# DualMonoPSU.net
KiCad netlist of a schematic drawn in EAGLE
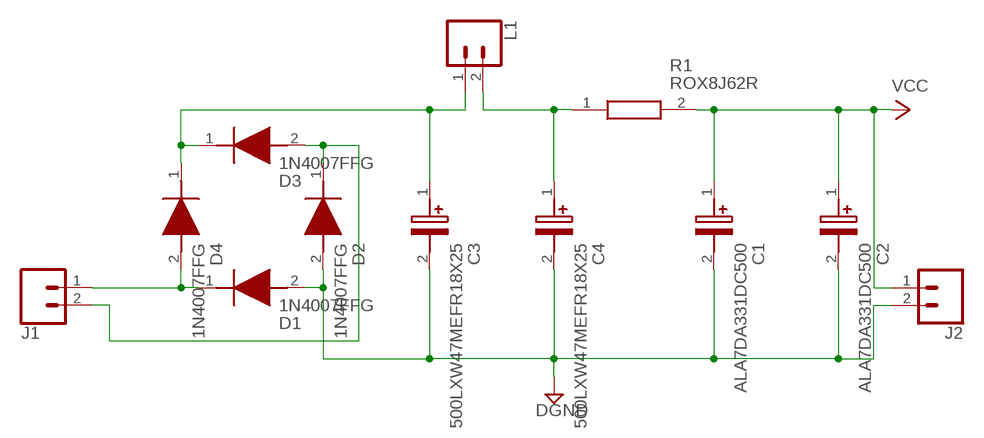
[diagram p0: schematic, sheet 1]

(export (version "E")
  (design (tool "Eeschema 10.0.6"))
  (components
    (comp (ref "C1")
      (value "ALA7DA331DC500")
      (footprint "eagle-import:ALA7DA331DC500")
      (fields (field (name "MOUSER_PART_NUMBER") "80-ALA7DA331DC500"))
      (libsource (lib "eagle-import") (part "ALA7DA331DC500"))
    )
    (comp (ref "C2")
      (value "ALA7DA331DC500")
      (footprint "eagle-import:ALA7DA331DC500")
      (fields (field (name "MOUSER_PART_NUMBER") "80-ALA7DA331DC500"))
      (libsource (lib "eagle-import") (part "ALA7DA331DC500"))
    )
    (comp (ref "C3")
      (value "500LXW47MEFR18X25")
      (footprint "eagle-import:CAPPRD750W80D1825H2700")
      (fields (field (name "MOUSER_PART_NUMBER") "232-500LXW47MEFR18X2"))
      (libsource (lib "eagle-import") (part "500LXW47MEFR18X25"))
    )
    (comp (ref "C4")
      (value "500LXW47MEFR18X25")
      (footprint "eagle-import:CAPPRD750W80D1825H2700")
      (fields (field (name "MOUSER_PART_NUMBER") "232-500LXW47MEFR18X2"))
      (libsource (lib "eagle-import") (part "500LXW47MEFR18X25"))
    )
    (comp (ref "D1")
      (value "1N4007FFG")
      (footprint "eagle-import:DIOAD1405W86L465D235")
      (fields (field (name "MOUSER_PART_NUMBER") "863-1N4007FFG"))
      (libsource (lib "eagle-import") (part "1N4007FFG"))
    )
    (comp (ref "D2")
      (value "1N4007FFG")
      (footprint "eagle-import:DIOAD1405W86L465D235")
      (fields (field (name "MOUSER_PART_NUMBER") "863-1N4007FFG"))
      (libsource (lib "eagle-import") (part "1N4007FFG"))
    )
    (comp (ref "D3")
      (value "1N4007FFG")
      (footprint "eagle-import:DIOAD1405W86L465D235")
      (fields (field (name "MOUSER_PART_NUMBER") "863-1N4007FFG"))
      (libsource (lib "eagle-import") (part "1N4007FFG"))
    )
    (comp (ref "D4")
      (value "1N4007FFG")
      (footprint "eagle-import:DIOAD1405W86L465D235")
      (fields (field (name "MOUSER_PART_NUMBER") "863-1N4007FFG"))
      (libsource (lib "eagle-import") (part "1N4007FFG"))
    )
    (comp (ref "J1")
      (value "CONN_025MM")
      (footprint "eagle-import:SCREWTERMINAL-5MM-2")
      (libsource (lib "eagle-import") (part "CONN_025MM"))
    )
    (comp (ref "J2")
      (value "CONN_025MM")
      (footprint "eagle-import:SCREWTERMINAL-5MM-2")
      (libsource (lib "eagle-import") (part "CONN_025MM"))
    )
    (comp (ref "L1")
      (value "CONN_025MM")
      (footprint "eagle-import:SCREWTERMINAL-5MM-2")
      (libsource (lib "eagle-import") (part "CONN_025MM"))
    )
    (comp (ref "R1")
      (value "ROX8J62R")
      (footprint "eagle-import:RESAD7500W80L4100D850")
      (libsource (lib "eagle-import") (part "ROX8J62R"))
    )
  )
  (nets
    (net (code "1") (name "DGND") (class "Default")
      (node (ref "C1") (pin "2") (pinfunction "-_2") (pintype "bidirectional"))
      (node (ref "C2") (pin "2") (pinfunction "-_2") (pintype "bidirectional"))
      (node (ref "C3") (pin "2") (pinfunction "-_2") (pintype "bidirectional"))
      (node (ref "C4") (pin "2") (pinfunction "-_2") (pintype "bidirectional"))
      (node (ref "D1") (pin "2") (pinfunction "A_2") (pintype "bidirectional"))
      (node (ref "D2") (pin "2") (pinfunction "A_2") (pintype "bidirectional"))
      (node (ref "J2") (pin "2") (pinfunction "2_2") (pintype "passive"))
    )
    (net (code "2") (name "Net-(C3-+)") (class "Default")
      (node (ref "C3") (pin "1") (pinfunction "+_1") (pintype "bidirectional"))
      (node (ref "D3") (pin "1") (pinfunction "K_1") (pintype "bidirectional"))
      (node (ref "D4") (pin "1") (pinfunction "K_1") (pintype "bidirectional"))
      (node (ref "L1") (pin "1") (pinfunction "1_1") (pintype "passive"))
    )
    (net (code "3") (name "Net-(C4-+)") (class "Default")
      (node (ref "C4") (pin "1") (pinfunction "+_1") (pintype "bidirectional"))
      (node (ref "L1") (pin "2") (pinfunction "2_2") (pintype "passive"))
      (node (ref "R1") (pin "1") (pinfunction "1_1") (pintype "bidirectional"))
    )
    (net (code "4") (name "Net-(D1-K)") (class "Default")
      (node (ref "D1") (pin "1") (pinfunction "K_1") (pintype "bidirectional"))
      (node (ref "D4") (pin "2") (pinfunction "A_2") (pintype "bidirectional"))
      (node (ref "J1") (pin "1") (pinfunction "1_1") (pintype "passive"))
    )
    (net (code "5") (name "Net-(D2-K)") (class "Default")
      (node (ref "D2") (pin "1") (pinfunction "K_1") (pintype "bidirectional"))
      (node (ref "D3") (pin "2") (pinfunction "A_2") (pintype "bidirectional"))
      (node (ref "J1") (pin "2") (pinfunction "2_2") (pintype "passive"))
    )
    (net (code "6") (name "VCC") (class "Default")
      (node (ref "C1") (pin "1") (pinfunction "+_1") (pintype "bidirectional"))
      (node (ref "C2") (pin "1") (pinfunction "+_1") (pintype "bidirectional"))
      (node (ref "J2") (pin "1") (pinfunction "1_1") (pintype "passive"))
      (node (ref "R1") (pin "2") (pinfunction "2_2") (pintype "bidirectional"))
    )
  )
)
